# SchematicSheet1.net
KiCad netlist of a schematic drawn in Altium Designer
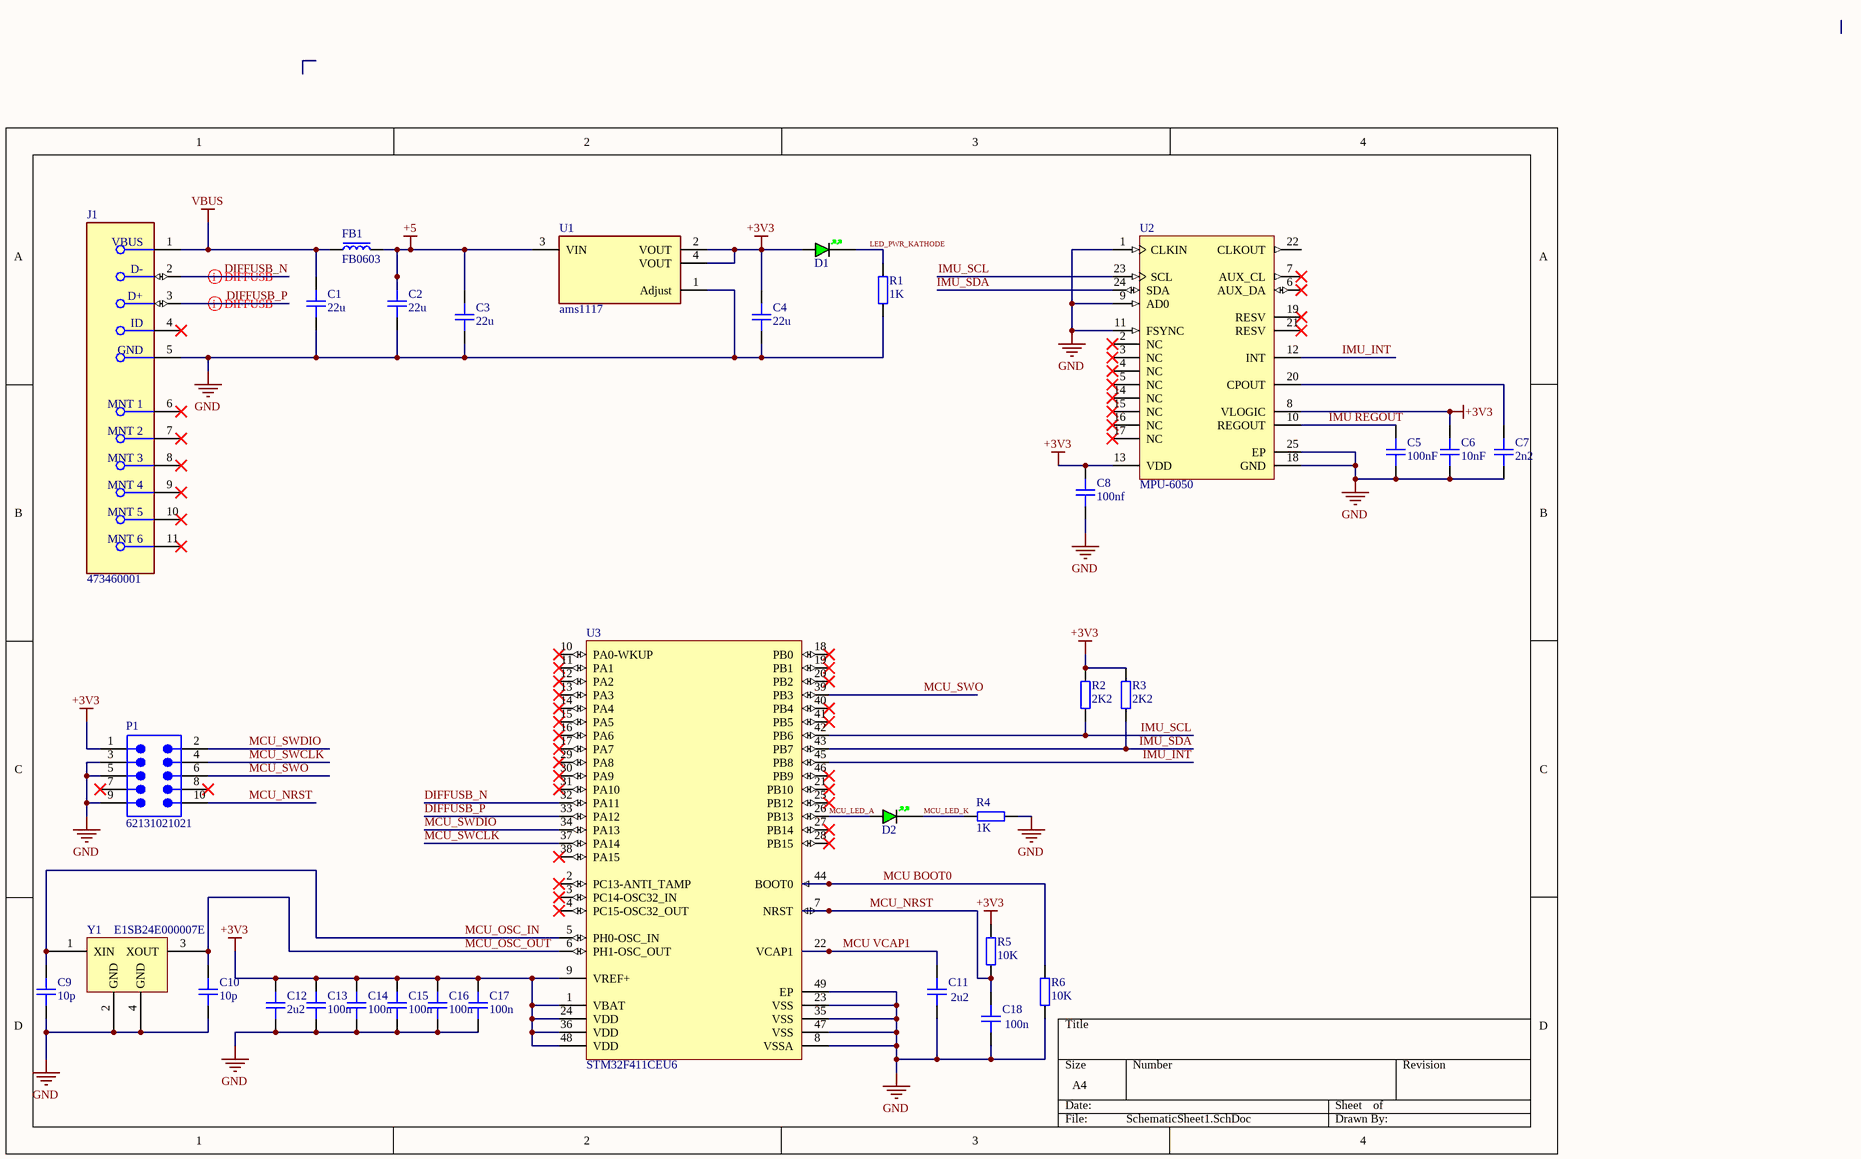
[diagram p0: SchematicSheet1.SchDoc]

(export (version "E")
  (design (tool "Eeschema 10.0.6"))
  (components
    (comp (ref "C1")
      (value "22u")
      (footprint "CAP_0805")
      (description "Capacitor SMD 0805")
      (libsource (lib "Schematic-Lib-PhilsLab") (part "CAP_0805"))
    )
    (comp (ref "C2")
      (value "22u")
      (footprint "CAP_0805")
      (description "Capacitor SMD 0805")
      (libsource (lib "Schematic-Lib-PhilsLab") (part "CAP_0805"))
    )
    (comp (ref "C3")
      (value "22u")
      (footprint "CAP_0805")
      (description "Capacitor SMD 0805")
      (libsource (lib "Schematic-Lib-PhilsLab") (part "CAP_0805"))
    )
    (comp (ref "C4")
      (value "22u")
      (footprint "CAP_0805")
      (description "Capacitor SMD 0805")
      (libsource (lib "Schematic-Lib-PhilsLab") (part "CAP_0805"))
    )
    (comp (ref "C5")
      (value "100nF")
      (footprint "CAP_0805")
      (description "Capacitor SMD 0805")
      (libsource (lib "Schematic-Lib-PhilsLab") (part "CAP_0805"))
    )
    (comp (ref "C6")
      (value "10nF")
      (footprint "CAP_0805")
      (description "Capacitor SMD 0805")
      (libsource (lib "Schematic-Lib-PhilsLab") (part "CAP_0805"))
    )
    (comp (ref "C7")
      (value "2n2")
      (footprint "CAP_0805")
      (description "Capacitor SMD 0805")
      (libsource (lib "Schematic-Lib-PhilsLab") (part "CAP_0805"))
    )
    (comp (ref "C8")
      (value "100nf")
      (footprint "CAP_0805")
      (description "Capacitor SMD 0805")
      (libsource (lib "Schematic-Lib-PhilsLab") (part "CAP_0805"))
    )
    (comp (ref "C9")
      (value "10p")
      (footprint "CAP_0805")
      (description "Capacitor SMD 0805")
      (libsource (lib "Schematic-Lib-PhilsLab") (part "CAP_0805"))
    )
    (comp (ref "C10")
      (value "10p")
      (footprint "CAP_0805")
      (description "Capacitor SMD 0805")
      (libsource (lib "Schematic-Lib-PhilsLab") (part "CAP_0805"))
    )
    (comp (ref "C11")
      (value "2u2")
      (footprint "CAP_0805")
      (description "Capacitor SMD 0805")
      (libsource (lib "Schematic-Lib-PhilsLab") (part "CAP_0805"))
    )
    (comp (ref "C12")
      (value "2u2")
      (footprint "CAP_0805")
      (description "Capacitor SMD 0805")
      (libsource (lib "Schematic-Lib-PhilsLab") (part "CAP_0805"))
    )
    (comp (ref "C13")
      (value "100n")
      (footprint "CAP_0805")
      (description "Capacitor SMD 0805")
      (libsource (lib "Schematic-Lib-PhilsLab") (part "CAP_0805"))
    )
    (comp (ref "C14")
      (value "100n")
      (footprint "CAP_0805")
      (description "Capacitor SMD 0805")
      (libsource (lib "Schematic-Lib-PhilsLab") (part "CAP_0805"))
    )
    (comp (ref "C15")
      (value "100n")
      (footprint "CAP_0805")
      (description "Capacitor SMD 0805")
      (libsource (lib "Schematic-Lib-PhilsLab") (part "CAP_0805"))
    )
    (comp (ref "C16")
      (value "100n")
      (footprint "CAP_0805")
      (description "Capacitor SMD 0805")
      (libsource (lib "Schematic-Lib-PhilsLab") (part "CAP_0805"))
    )
    (comp (ref "C17")
      (value "100n")
      (footprint "CAP_0805")
      (description "Capacitor SMD 0805")
      (libsource (lib "Schematic-Lib-PhilsLab") (part "CAP_0805"))
    )
    (comp (ref "C18")
      (value "100n")
      (footprint "CAP_0805")
      (description "Capacitor SMD 0805")
      (libsource (lib "Schematic-Lib-PhilsLab") (part "CAP_0805"))
    )
    (comp (ref "D1")
      (value "GREEN")
      (footprint "LED_0402_GREEN")
      (description "LED 0402 GREEN SMD")
      (libsource (lib "Schematic-Lib-PhilsLab") (part "LED_0402_GREEN"))
    )
    (comp (ref "D2")
      (value "GREEN")
      (footprint "LED_0402_GREEN")
      (description "LED 0402 GREEN SMD")
      (libsource (lib "Schematic-Lib-PhilsLab") (part "LED_0402_GREEN"))
    )
    (comp (ref "FB1")
      (value "FB0603")
      (footprint "FB_0603")
      (description "Ferrite Bead SMD 0603")
      (libsource (lib "Schematic-Lib-PhilsLab") (part "FB_0603"))
    )
    (comp (ref "J1")
      (value "473460001")
      (footprint "FP-473460001-MFG")
      (description "CONN RCPT USB2.0 MICRO B SMD R/A")
      (fields
        (field (name "OCTOPART") "https://octopart.com/47346-0001-molex-7164928")
        (field (name "MANUFACTURER") "Molex")
      )
      (libsource (lib "Altium Content Vault") (part "53ae1f1d9b557310b43ca686e5bb76a"))
    )
    (comp (ref "P1")
      (value "62131021021")
      (footprint "62131021021")
      (libsource (lib "Altium Content Vault") (part "Header_Male_2R_10P"))
    )
    (comp (ref "R1")
      (value "1K")
      (footprint "RES_0402")
      (description "Resistor SMD 0402")
      (libsource (lib "Schematic-Lib-PhilsLab") (part "RES_0402"))
    )
    (comp (ref "R2")
      (value "2K2")
      (footprint "RES_0402")
      (description "Resistor SMD 0402")
      (libsource (lib "Schematic-Lib-PhilsLab") (part "RES_0402"))
    )
    (comp (ref "R3")
      (value "2K2")
      (footprint "RES_0402")
      (description "Resistor SMD 0402")
      (libsource (lib "Schematic-Lib-PhilsLab") (part "RES_0402"))
    )
    (comp (ref "R4")
      (value "1K")
      (footprint "RES_0402")
      (description "Resistor SMD 0402")
      (libsource (lib "Schematic-Lib-PhilsLab") (part "RES_0402"))
    )
    (comp (ref "R5")
      (value "10K")
      (footprint "RES_0402")
      (description "Resistor SMD 0402")
      (libsource (lib "Schematic-Lib-PhilsLab") (part "RES_0402"))
    )
    (comp (ref "R6")
      (value "10K")
      (footprint "RES_0402")
      (description "Resistor SMD 0402")
      (libsource (lib "Schematic-Lib-PhilsLab") (part "RES_0402"))
    )
    (comp (ref "U1")
      (value "ams1117")
      (footprint "FP-ams1117-IPC_C")
      (description "1A LOW DROPOUT VOLTAGE REGULATOR")
      (libsource (lib "Altium Content Vault") (part "59ad430b93a2c51b3e6ee7c3b069677"))
    )
    (comp (ref "U2")
      (value "MPU-6050")
      (footprint "IS-QFN-24_V")
      (fields (field (name "MANUFACTURER") "InvenSense"))
      (libsource (lib "Altium Content Vault") (part "IS-MPU-6050-QFN-24"))
    )
    (comp (ref "U3")
      (value "STM32F411CEU6")
      (footprint "STM-UFQFPN48_L")
      (libsource (lib "Altium Content Vault") (part "MC-ARM-STM32F411-UFQFPN48"))
    )
    (comp (ref "Y1")
      (value "E1SB24E000007E")
      (footprint "TROQ R940000171")
      (description "24MHz 9pF ±10ppm SMD2016-4P Crystals ROHS")
      (libsource (lib "MaryLab Projets") (part "E1SB24E000007E"))
    )
  )
  (nets
    (net (code "1") (name "+3V3") (class "Default")
      (node (ref "C12") (pin "2") (pinfunction "2_2") (pintype "passive"))
      (node (ref "C13") (pin "2") (pinfunction "2_2") (pintype "passive"))
      (node (ref "C14") (pin "2") (pinfunction "2_2") (pintype "passive"))
      (node (ref "C15") (pin "2") (pinfunction "2_2") (pintype "passive"))
      (node (ref "C16") (pin "2") (pinfunction "2_2") (pintype "passive"))
      (node (ref "C17") (pin "2") (pinfunction "2_2") (pintype "passive"))
      (node (ref "C4") (pin "2") (pinfunction "2_2") (pintype "passive"))
      (node (ref "C6") (pin "2") (pinfunction "2_2") (pintype "passive"))
      (node (ref "C8") (pin "2") (pinfunction "2_2") (pintype "passive"))
      (node (ref "D1") (pin "A") (pinfunction "A_A") (pintype "passive"))
      (node (ref "P1") (pin "1") (pinfunction "1_1") (pintype "passive"))
      (node (ref "R2") (pin "2") (pinfunction "2_2") (pintype "passive"))
      (node (ref "R3") (pin "2") (pinfunction "2_2") (pintype "passive"))
      (node (ref "R5") (pin "1") (pinfunction "1_1") (pintype "passive"))
      (node (ref "U1") (pin "2") (pinfunction "VOUT_2") (pintype "passive"))
      (node (ref "U1") (pin "4") (pinfunction "VOUT_4") (pintype "passive"))
      (node (ref "U2") (pin "13") (pinfunction "VDD_13") (pintype "power_in"))
      (node (ref "U2") (pin "8") (pinfunction "VLOGIC_8") (pintype "power_in"))
      (node (ref "U3") (pin "1") (pinfunction "VBAT_1") (pintype "power_in"))
      (node (ref "U3") (pin "24") (pinfunction "VDD_24") (pintype "power_in"))
      (node (ref "U3") (pin "36") (pinfunction "VDD_36") (pintype "power_in"))
      (node (ref "U3") (pin "48") (pinfunction "VDD_48") (pintype "power_in"))
      (node (ref "U3") (pin "9") (pinfunction "VREF+_9") (pintype "power_in"))
    )
    (net (code "2") (name "+5") (class "Default")
      (node (ref "C2") (pin "2") (pinfunction "2_2") (pintype "passive"))
      (node (ref "C3") (pin "2") (pinfunction "2_2") (pintype "passive"))
      (node (ref "FB1") (pin "2") (pinfunction "2_2") (pintype "passive"))
      (node (ref "U1") (pin "3") (pinfunction "VIN_3") (pintype "power_in"))
    )
    (net (code "3") (name "/DIFFUSB_N") (class "Default")
      (node (ref "J1") (pin "2") (pinfunction "D-_2") (pintype "bidirectional"))
      (node (ref "U3") (pin "32") (pinfunction "PA11_32") (pintype "bidirectional"))
    )
    (net (code "4") (name "/DIFFUSB_P") (class "Default")
      (node (ref "J1") (pin "3") (pinfunction "D+_3") (pintype "bidirectional"))
      (node (ref "U3") (pin "33") (pinfunction "PA12_33") (pintype "bidirectional"))
    )
    (net (code "5") (name "/IMU REGOUT") (class "Default")
      (node (ref "C5") (pin "2") (pinfunction "2_2") (pintype "passive"))
      (node (ref "U2") (pin "10") (pinfunction "REGOUT_10") (pintype "passive"))
    )
    (net (code "6") (name "/IMU_INT") (class "Default")
      (node (ref "U2") (pin "12") (pinfunction "INT_12") (pintype "open_collector"))
      (node (ref "U3") (pin "45") (pinfunction "PB8_45") (pintype "bidirectional"))
    )
    (net (code "7") (name "/IMU_SCL") (class "Default")
      (node (ref "R2") (pin "1") (pinfunction "1_1") (pintype "passive"))
      (node (ref "U2") (pin "23") (pinfunction "SCL_23") (pintype "input"))
      (node (ref "U3") (pin "42") (pinfunction "PB6_42") (pintype "bidirectional"))
    )
    (net (code "8") (name "/IMU_SDA") (class "Default")
      (node (ref "R3") (pin "1") (pinfunction "1_1") (pintype "passive"))
      (node (ref "U2") (pin "24") (pinfunction "SDA_24") (pintype "bidirectional"))
      (node (ref "U3") (pin "43") (pinfunction "PB7_43") (pintype "bidirectional"))
    )
    (net (code "9") (name "/LED_PWR_KATHODE") (class "Default")
      (node (ref "D1") (pin "K") (pinfunction "K_K") (pintype "passive"))
      (node (ref "R1") (pin "2") (pinfunction "2_2") (pintype "passive"))
    )
    (net (code "10") (name "/MCU BOOT0") (class "Default")
      (node (ref "R6") (pin "1") (pinfunction "1_1") (pintype "passive"))
      (node (ref "U3") (pin "44") (pinfunction "BOOT0_44") (pintype "input"))
    )
    (net (code "11") (name "/MCU VCAP1") (class "Default")
      (node (ref "C11") (pin "2") (pinfunction "2_2") (pintype "passive"))
      (node (ref "U3") (pin "22") (pinfunction "VCAP1_22") (pintype "passive"))
    )
    (net (code "12") (name "/MCU_LED_A") (class "Default")
      (node (ref "D2") (pin "A") (pinfunction "A_A") (pintype "passive"))
      (node (ref "U3") (pin "26") (pinfunction "PB13_26") (pintype "bidirectional"))
    )
    (net (code "13") (name "/MCU_LED_K") (class "Default")
      (node (ref "D2") (pin "K") (pinfunction "K_K") (pintype "passive"))
      (node (ref "R4") (pin "2") (pinfunction "2_2") (pintype "passive"))
    )
    (net (code "14") (name "/MCU_NRST") (class "Default")
      (node (ref "C18") (pin "2") (pinfunction "2_2") (pintype "passive"))
      (node (ref "P1") (pin "10") (pinfunction "10_10") (pintype "passive"))
      (node (ref "R5") (pin "2") (pinfunction "2_2") (pintype "passive"))
      (node (ref "U3") (pin "7") (pinfunction "NRST_7") (pintype "bidirectional"))
    )
    (net (code "15") (name "/MCU_OSC_IN") (class "Default")
      (node (ref "C9") (pin "2") (pinfunction "2_2") (pintype "passive"))
      (node (ref "U3") (pin "5") (pinfunction "PH0-OSC_IN_5") (pintype "bidirectional"))
      (node (ref "Y1") (pin "1") (pinfunction "XIN_1") (pintype "passive"))
    )
    (net (code "16") (name "/MCU_OSC_OUT") (class "Default")
      (node (ref "C10") (pin "2") (pinfunction "2_2") (pintype "passive"))
      (node (ref "U3") (pin "6") (pinfunction "PH1-OSC_OUT_6") (pintype "bidirectional"))
      (node (ref "Y1") (pin "3") (pinfunction "XOUT_3") (pintype "passive"))
    )
    (net (code "17") (name "/MCU_SWCLK") (class "Default")
      (node (ref "P1") (pin "4") (pinfunction "4_4") (pintype "passive"))
      (node (ref "U3") (pin "37") (pinfunction "PA14_37") (pintype "bidirectional"))
    )
    (net (code "18") (name "/MCU_SWDIO") (class "Default")
      (node (ref "P1") (pin "2") (pinfunction "2_2") (pintype "passive"))
      (node (ref "U3") (pin "34") (pinfunction "PA13_34") (pintype "bidirectional"))
    )
    (net (code "19") (name "/MCU_SWO") (class "Default")
      (node (ref "P1") (pin "6") (pinfunction "6_6") (pintype "passive"))
      (node (ref "U3") (pin "39") (pinfunction "PB3_39") (pintype "bidirectional"))
    )
    (net (code "20") (name "GND") (class "Default")
      (node (ref "C1") (pin "1") (pinfunction "1_1") (pintype "passive"))
      (node (ref "C10") (pin "1") (pinfunction "1_1") (pintype "passive"))
      (node (ref "C11") (pin "1") (pinfunction "1_1") (pintype "passive"))
      (node (ref "C12") (pin "1") (pinfunction "1_1") (pintype "passive"))
      (node (ref "C13") (pin "1") (pinfunction "1_1") (pintype "passive"))
      (node (ref "C14") (pin "1") (pinfunction "1_1") (pintype "passive"))
      (node (ref "C15") (pin "1") (pinfunction "1_1") (pintype "passive"))
      (node (ref "C16") (pin "1") (pinfunction "1_1") (pintype "passive"))
      (node (ref "C17") (pin "1") (pinfunction "1_1") (pintype "passive"))
      (node (ref "C18") (pin "1") (pinfunction "1_1") (pintype "passive"))
      (node (ref "C2") (pin "1") (pinfunction "1_1") (pintype "passive"))
      (node (ref "C3") (pin "1") (pinfunction "1_1") (pintype "passive"))
      (node (ref "C4") (pin "1") (pinfunction "1_1") (pintype "passive"))
      (node (ref "C5") (pin "1") (pinfunction "1_1") (pintype "passive"))
      (node (ref "C6") (pin "1") (pinfunction "1_1") (pintype "passive"))
      (node (ref "C7") (pin "1") (pinfunction "1_1") (pintype "passive"))
      (node (ref "C8") (pin "1") (pinfunction "1_1") (pintype "passive"))
      (node (ref "C9") (pin "1") (pinfunction "1_1") (pintype "passive"))
      (node (ref "J1") (pin "5") (pinfunction "GND_5") (pintype "power_in"))
      (node (ref "P1") (pin "3") (pinfunction "3_3") (pintype "passive"))
      (node (ref "P1") (pin "5") (pinfunction "5_5") (pintype "passive"))
      (node (ref "P1") (pin "9") (pinfunction "9_9") (pintype "passive"))
      (node (ref "R1") (pin "1") (pinfunction "1_1") (pintype "passive"))
      (node (ref "R4") (pin "1") (pinfunction "1_1") (pintype "passive"))
      (node (ref "R6") (pin "2") (pinfunction "2_2") (pintype "passive"))
      (node (ref "U1") (pin "1") (pinfunction "Adjust_1") (pintype "passive"))
      (node (ref "U2") (pin "1") (pinfunction "CLKIN_1") (pintype "input"))
      (node (ref "U2") (pin "11") (pinfunction "FSYNC_11") (pintype "input"))
      (node (ref "U2") (pin "18") (pinfunction "GND_18") (pintype "power_in"))
      (node (ref "U2") (pin "25") (pinfunction "EP_25") (pintype "power_in"))
      (node (ref "U2") (pin "9") (pinfunction "AD0_9") (pintype "input"))
      (node (ref "U3") (pin "23") (pinfunction "VSS_23") (pintype "power_in"))
      (node (ref "U3") (pin "35") (pinfunction "VSS_35") (pintype "power_in"))
      (node (ref "U3") (pin "47") (pinfunction "VSS_47") (pintype "power_in"))
      (node (ref "U3") (pin "49") (pinfunction "EP_49") (pintype "power_in"))
      (node (ref "U3") (pin "8") (pinfunction "VSSA_8") (pintype "power_in"))
      (node (ref "Y1") (pin "2") (pinfunction "GND_2") (pintype "passive"))
      (node (ref "Y1") (pin "4") (pinfunction "GND_4") (pintype "passive"))
    )
    (net (code "21") (name "Net-(U2-CPOUT)") (class "Default")
      (node (ref "C7") (pin "2") (pinfunction "2_2") (pintype "passive"))
      (node (ref "U2") (pin "20") (pinfunction "CPOUT_20") (pintype "passive"))
    )
    (net (code "22") (name "VBUS") (class "Default")
      (node (ref "C1") (pin "2") (pinfunction "2_2") (pintype "passive"))
      (node (ref "FB1") (pin "1") (pinfunction "1_1") (pintype "passive"))
      (node (ref "J1") (pin "1") (pinfunction "VBUS_1") (pintype "power_in"))
    )
    (net (code "23") (name "unconnected-(J1-ID-Pad4)") (class "Default")
      (node (ref "J1") (pin "4") (pinfunction "ID_4") (pintype "passive+no_connect"))
    )
    (net (code "24") (name "unconnected-(J1-MNT_1-Pad6)") (class "Default")
      (node (ref "J1") (pin "6") (pinfunction "MNT_1_6") (pintype "passive+no_connect"))
    )
    (net (code "25") (name "unconnected-(J1-MNT_2-Pad7)") (class "Default")
      (node (ref "J1") (pin "7") (pinfunction "MNT_2_7") (pintype "passive+no_connect"))
    )
    (net (code "26") (name "unconnected-(J1-MNT_3-Pad8)") (class "Default")
      (node (ref "J1") (pin "8") (pinfunction "MNT_3_8") (pintype "passive+no_connect"))
    )
    (net (code "27") (name "unconnected-(J1-MNT_4-Pad9)") (class "Default")
      (node (ref "J1") (pin "9") (pinfunction "MNT_4_9") (pintype "passive+no_connect"))
    )
    (net (code "28") (name "unconnected-(J1-MNT_5-Pad10)") (class "Default")
      (node (ref "J1") (pin "10") (pinfunction "MNT_5_10") (pintype "passive+no_connect"))
    )
    (net (code "29") (name "unconnected-(J1-MNT_6-Pad11)") (class "Default")
      (node (ref "J1") (pin "11") (pinfunction "MNT_6_11") (pintype "passive+no_connect"))
    )
    (net (code "30") (name "unconnected-(P1-Pad7)") (class "Default")
      (node (ref "P1") (pin "7") (pinfunction "7_7") (pintype "passive+no_connect"))
    )
    (net (code "31") (name "unconnected-(P1-Pad8)") (class "Default")
      (node (ref "P1") (pin "8") (pinfunction "8_8") (pintype "passive+no_connect"))
    )
    (net (code "32") (name "unconnected-(U2-AUX_CL-Pad7)") (class "Default")
      (node (ref "U2") (pin "7") (pinfunction "AUX_CL_7") (pintype "output+no_connect"))
    )
    (net (code "33") (name "unconnected-(U2-AUX_DA-Pad6)") (class "Default")
      (node (ref "U2") (pin "6") (pinfunction "AUX_DA_6") (pintype "bidirectional+no_connect"))
    )
    (net (code "34") (name "unconnected-(U2-CLKOUT-Pad22)") (class "Default")
      (node (ref "U2") (pin "22") (pinfunction "CLKOUT_22") (pintype "output"))
    )
    (net (code "35") (name "unconnected-(U2-NC-Pad2)") (class "Default")
      (node (ref "U2") (pin "2") (pinfunction "NC_2") (pintype "passive+no_connect"))
    )
    (net (code "36") (name "unconnected-(U2-NC-Pad3)") (class "Default")
      (node (ref "U2") (pin "3") (pinfunction "NC_3") (pintype "passive+no_connect"))
    )
    (net (code "37") (name "unconnected-(U2-NC-Pad4)") (class "Default")
      (node (ref "U2") (pin "4") (pinfunction "NC_4") (pintype "passive+no_connect"))
    )
    (net (code "38") (name "unconnected-(U2-NC-Pad5)") (class "Default")
      (node (ref "U2") (pin "5") (pinfunction "NC_5") (pintype "passive+no_connect"))
    )
    (net (code "39") (name "unconnected-(U2-NC-Pad14)") (class "Default")
      (node (ref "U2") (pin "14") (pinfunction "NC_14") (pintype "passive+no_connect"))
    )
    (net (code "40") (name "unconnected-(U2-NC-Pad15)") (class "Default")
      (node (ref "U2") (pin "15") (pinfunction "NC_15") (pintype "passive+no_connect"))
    )
    (net (code "41") (name "unconnected-(U2-NC-Pad16)") (class "Default")
      (node (ref "U2") (pin "16") (pinfunction "NC_16") (pintype "passive+no_connect"))
    )
    (net (code "42") (name "unconnected-(U2-NC-Pad17)") (class "Default")
      (node (ref "U2") (pin "17") (pinfunction "NC_17") (pintype "passive+no_connect"))
    )
    (net (code "43") (name "unconnected-(U2-RESV-Pad19)") (class "Default")
      (node (ref "U2") (pin "19") (pinfunction "RESV_19") (pintype "passive+no_connect"))
    )
    (net (code "44") (name "unconnected-(U2-RESV-Pad21)") (class "Default")
      (node (ref "U2") (pin "21") (pinfunction "RESV_21") (pintype "passive+no_connect"))
    )
    (net (code "45") (name "unconnected-(U3-PA0-WKUP-Pad10)") (class "Default")
      (node (ref "U3") (pin "10") (pinfunction "PA0-WKUP_10") (pintype "bidirectional+no_connect"))
    )
    (net (code "46") (name "unconnected-(U3-PA1-Pad11)") (class "Default")
      (node (ref "U3") (pin "11") (pinfunction "PA1_11") (pintype "bidirectional+no_connect"))
    )
    (net (code "47") (name "unconnected-(U3-PA2-Pad12)") (class "Default")
      (node (ref "U3") (pin "12") (pinfunction "PA2_12") (pintype "bidirectional+no_connect"))
    )
    (net (code "48") (name "unconnected-(U3-PA3-Pad13)") (class "Default")
      (node (ref "U3") (pin "13") (pinfunction "PA3_13") (pintype "bidirectional+no_connect"))
    )
    (net (code "49") (name "unconnected-(U3-PA4-Pad14)") (class "Default")
      (node (ref "U3") (pin "14") (pinfunction "PA4_14") (pintype "bidirectional+no_connect"))
    )
    (net (code "50") (name "unconnected-(U3-PA5-Pad15)") (class "Default")
      (node (ref "U3") (pin "15") (pinfunction "PA5_15") (pintype "bidirectional+no_connect"))
    )
    (net (code "51") (name "unconnected-(U3-PA6-Pad16)") (class "Default")
      (node (ref "U3") (pin "16") (pinfunction "PA6_16") (pintype "bidirectional+no_connect"))
    )
    (net (code "52") (name "unconnected-(U3-PA7-Pad17)") (class "Default")
      (node (ref "U3") (pin "17") (pinfunction "PA7_17") (pintype "bidirectional+no_connect"))
    )
    (net (code "53") (name "unconnected-(U3-PA8-Pad29)") (class "Default")
      (node (ref "U3") (pin "29") (pinfunction "PA8_29") (pintype "bidirectional+no_connect"))
    )
    (net (code "54") (name "unconnected-(U3-PA9-Pad30)") (class "Default")
      (node (ref "U3") (pin "30") (pinfunction "PA9_30") (pintype "bidirectional+no_connect"))
    )
    (net (code "55") (name "unconnected-(U3-PA10-Pad31)") (class "Default")
      (node (ref "U3") (pin "31") (pinfunction "PA10_31") (pintype "bidirectional+no_connect"))
    )
    (net (code "56") (name "unconnected-(U3-PA15-Pad38)") (class "Default")
      (node (ref "U3") (pin "38") (pinfunction "PA15_38") (pintype "bidirectional+no_connect"))
    )
    (net (code "57") (name "unconnected-(U3-PB0-Pad18)") (class "Default")
      (node (ref "U3") (pin "18") (pinfunction "PB0_18") (pintype "bidirectional+no_connect"))
    )
    (net (code "58") (name "unconnected-(U3-PB1-Pad19)") (class "Default")
      (node (ref "U3") (pin "19") (pinfunction "PB1_19") (pintype "bidirectional+no_connect"))
    )
    (net (code "59") (name "unconnected-(U3-PB2-Pad20)") (class "Default")
      (node (ref "U3") (pin "20") (pinfunction "PB2_20") (pintype "bidirectional+no_connect"))
    )
    (net (code "60") (name "unconnected-(U3-PB4-Pad40)") (class "Default")
      (node (ref "U3") (pin "40") (pinfunction "PB4_40") (pintype "bidirectional+no_connect"))
    )
    (net (code "61") (name "unconnected-(U3-PB5-Pad41)") (class "Default")
      (node (ref "U3") (pin "41") (pinfunction "PB5_41") (pintype "bidirectional+no_connect"))
    )
    (net (code "62") (name "unconnected-(U3-PB9-Pad46)") (class "Default")
      (node (ref "U3") (pin "46") (pinfunction "PB9_46") (pintype "bidirectional+no_connect"))
    )
    (net (code "63") (name "unconnected-(U3-PB10-Pad21)") (class "Default")
      (node (ref "U3") (pin "21") (pinfunction "PB10_21") (pintype "bidirectional+no_connect"))
    )
    (net (code "64") (name "unconnected-(U3-PB12-Pad25)") (class "Default")
      (node (ref "U3") (pin "25") (pinfunction "PB12_25") (pintype "bidirectional+no_connect"))
    )
    (net (code "65") (name "unconnected-(U3-PB14-Pad27)") (class "Default")
      (node (ref "U3") (pin "27") (pinfunction "PB14_27") (pintype "bidirectional+no_connect"))
    )
    (net (code "66") (name "unconnected-(U3-PB15-Pad28)") (class "Default")
      (node (ref "U3") (pin "28") (pinfunction "PB15_28") (pintype "bidirectional+no_connect"))
    )
    (net (code "67") (name "unconnected-(U3-PC13-ANTI_TAMP-Pad2)") (class "Default")
      (node (ref "U3") (pin "2") (pinfunction "PC13-ANTI_TAMP_2") (pintype "bidirectional+no_connect"))
    )
    (net (code "68") (name "unconnected-(U3-PC14-OSC32_IN-Pad3)") (class "Default")
      (node (ref "U3") (pin "3") (pinfunction "PC14-OSC32_IN_3") (pintype "bidirectional+no_connect"))
    )
    (net (code "69") (name "unconnected-(U3-PC15-OSC32_OUT-Pad4)") (class "Default")
      (node (ref "U3") (pin "4") (pinfunction "PC15-OSC32_OUT_4") (pintype "bidirectional+no_connect"))
    )
  )
)
